# Sheet.net
KiCad netlist of a schematic drawn in Altium Designer
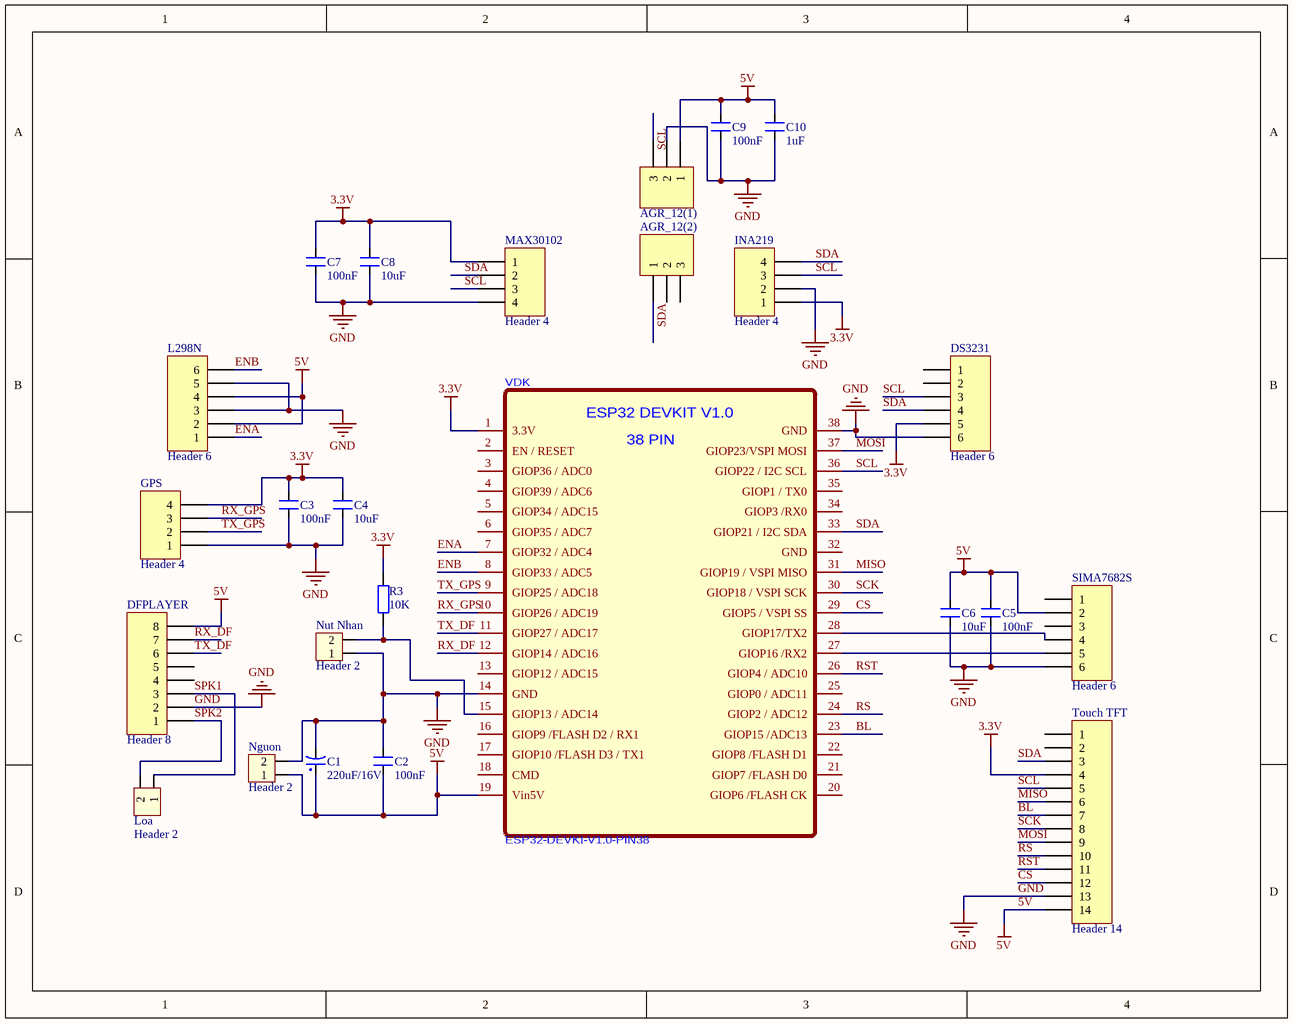
[diagram p0: Sheet.SchDoc]

(export (version "E")
  (design (tool "Eeschema 10.0.6"))
  (components
    (comp (ref "AGR_12(1)")
      (value "~")
      (footprint "HDR1X3")
      (description "Header, 3-Pin")
      (fields (field (name "PUBLISHER") "Altium Limited"))
      (libsource (lib "") (part "Header 3_1"))
    )
    (comp (ref "AGR_12(2)")
      (value "~")
      (footprint "HDR1X3")
      (description "Header, 3-Pin")
      (fields (field (name "PUBLISHER") "Altium Limited"))
      (libsource (lib "Altium_Devzone") (part "Header 3"))
    )
    (comp (ref "C1")
      (value "220uF/16V")
      (footprint "CP1.5/3.4")
      (description "Cap 1000uF/16V - 220uF/50V")
      (libsource (lib "My Library") (part "CP4"))
    )
    (comp (ref "C2")
      (value "100nF")
      (footprint "CN2")
      (description "Cap np 104 => 105pF")
      (libsource (lib "Altium_Devzone") (part "CN2"))
    )
    (comp (ref "C3")
      (value "100nF")
      (footprint "CN2")
      (description "Cap np 104 => 105pF")
      (libsource (lib "Altium_Devzone") (part "CN2"))
    )
    (comp (ref "C4")
      (value "10uF")
      (footprint "CN2")
      (description "Cap np 104 => 105pF")
      (libsource (lib "Altium_Devzone") (part "CN2"))
    )
    (comp (ref "C5")
      (value "100nF")
      (footprint "CN2")
      (description "Cap np 104 => 105pF")
      (libsource (lib "Altium_Devzone") (part "CN2"))
    )
    (comp (ref "C6")
      (value "10uF")
      (footprint "CN2")
      (description "Cap np 104 => 105pF")
      (libsource (lib "Altium_Devzone") (part "CN2"))
    )
    (comp (ref "C7")
      (value "100nF")
      (footprint "CN2")
      (description "Cap np 104 => 105pF")
      (libsource (lib "Altium_Devzone") (part "CN2"))
    )
    (comp (ref "C8")
      (value "10uF")
      (footprint "CN2")
      (description "Cap np 104 => 105pF")
      (libsource (lib "Altium_Devzone") (part "CN2"))
    )
    (comp (ref "C9")
      (value "100nF")
      (footprint "CN2")
      (description "Cap np 104 => 105pF")
      (libsource (lib "Altium_Devzone") (part "CN2"))
    )
    (comp (ref "C10")
      (value "1uF")
      (footprint "CN2")
      (description "Cap np 104 => 105pF")
      (libsource (lib "Altium_Devzone") (part "CN2"))
    )
    (comp (ref "DFPLAYER")
      (value "Header 8")
      (footprint "HDR1X8")
      (description "Header, 8-Pin")
      (fields (field (name "PUBLISHER") "Altium Limited"))
      (libsource (lib "Altium_Devzone") (part "Header 8"))
    )
    (comp (ref "DS3231")
      (value "Header 6")
      (footprint "HDR1X6")
      (description "Header, 6-Pin")
      (fields (field (name "PUBLISHER") "Altium Limited"))
      (libsource (lib "My Library") (part "Header 6"))
    )
    (comp (ref "GPS")
      (value "Header 4")
      (footprint "HDR1X4")
      (description "Header, 4-Pin")
      (fields (field (name "PUBLISHER") "Altium Limited"))
      (libsource (lib "") (part "Header 4_1"))
    )
    (comp (ref "INA219")
      (value "Header 4")
      (footprint "HDR1X4")
      (description "Header, 4-Pin")
      (fields (field (name "PUBLISHER") "Altium Limited"))
      (libsource (lib "") (part "Header 4_1"))
    )
    (comp (ref "L298N")
      (value "Header 6")
      (footprint "HDR1X6")
      (description "Header, 6-Pin")
      (fields (field (name "PUBLISHER") "Altium Limited"))
      (libsource (lib "Altium_Devzone") (part "Header 6"))
    )
    (comp (ref "Loa")
      (value "Header 2")
      (footprint "HED2")
      (description "Header 2 (Green)")
      (libsource (lib "") (part "Hed2_1"))
    )
    (comp (ref "MAX30102")
      (value "Header 4")
      (footprint "HDR1X4")
      (description "Header, 4-Pin")
      (fields (field (name "PUBLISHER") "Altium Limited"))
      (libsource (lib "My Library") (part "Header 4"))
    )
    (comp (ref "Nguon")
      (value "Header 2")
      (footprint "HED2")
      (description "Header 2 (Green)")
      (libsource (lib "My Library") (part "Hed2"))
    )
    (comp (ref "Nut Nhan")
      (value "Header 2")
      (footprint "HED2")
      (description "Header 2 (Green)")
      (libsource (lib "My Library") (part "Hed2"))
    )
    (comp (ref "R3")
      (value "10K")
      (footprint "DIEN TRO 1/4 W")
      (description "Resistor")
      (fields (field (name "Comment") "R0.4W") (field (name "PUBLISHER") "Altium Limited"))
      (libsource (lib "Altium_Devzone") (part "Res 1/4 W"))
    )
    (comp (ref "SIMA7682S")
      (value "Header 6")
      (footprint "HDR1X6")
      (description "Header, 6-Pin")
      (fields (field (name "PUBLISHER") "Altium Limited"))
      (libsource (lib "My Library") (part "Header 6"))
    )
    (comp (ref "Touch TFT")
      (value "Header 14")
      (footprint "HDR1X14")
      (description "Header, 14-Pin")
      (fields (field (name "PUBLISHER") "Altium Limited"))
      (libsource (lib "My Library") (part "Header 14"))
    )
    (comp (ref "VDK")
      (value "ESP32-DEVKI-V1.0-PIN38")
      (footprint "ESP32-DEVKIT-V1.0-38PIN")
      (libsource (lib "My Library") (part "ESP32-DEVKI-V1.0-PIN38"))
    )
  )
  (nets
    (net (code "1") (name "/BL") (class "Default")
      (node (ref "Touch TFT") (pin "7") (pinfunction "7_7") (pintype "passive"))
      (node (ref "VDK") (pin "23") (pinfunction "GIOP15_/ADC13_23") (pintype "passive"))
    )
    (net (code "2") (name "/CS") (class "Default")
      (node (ref "Touch TFT") (pin "12") (pinfunction "12_12") (pintype "passive"))
      (node (ref "VDK") (pin "29") (pinfunction "GIOP5_/_VSPI_SS_29") (pintype "passive"))
    )
    (net (code "3") (name "/ENA") (class "Default")
      (node (ref "L298N") (pin "1") (pinfunction "1_1") (pintype "passive"))
      (node (ref "VDK") (pin "7") (pinfunction "GIOP32_/_ADC4_7") (pintype "passive"))
    )
    (net (code "4") (name "/ENB") (class "Default")
      (node (ref "L298N") (pin "6") (pinfunction "6_6") (pintype "passive"))
      (node (ref "VDK") (pin "8") (pinfunction "GIOP33_/_ADC5_8") (pintype "passive"))
    )
    (net (code "5") (name "/MISO") (class "Default")
      (node (ref "Touch TFT") (pin "6") (pinfunction "6_6") (pintype "passive"))
      (node (ref "VDK") (pin "31") (pinfunction "GIOP19_/_VSPI_MISO_31") (pintype "passive"))
    )
    (net (code "6") (name "/MOSI") (class "Default")
      (node (ref "Touch TFT") (pin "9") (pinfunction "9_9") (pintype "passive"))
      (node (ref "VDK") (pin "37") (pinfunction "GIOP23/VSPI_MOSI_37") (pintype "passive"))
    )
    (net (code "7") (name "/RS") (class "Default")
      (node (ref "Touch TFT") (pin "10") (pinfunction "10_10") (pintype "passive"))
      (node (ref "VDK") (pin "24") (pinfunction "GIOP2_/_ADC12_24") (pintype "passive"))
    )
    (net (code "8") (name "/RST") (class "Default")
      (node (ref "Touch TFT") (pin "11") (pinfunction "11_11") (pintype "passive"))
      (node (ref "VDK") (pin "26") (pinfunction "GIOP4_/_ADC10_26") (pintype "passive"))
    )
    (net (code "9") (name "/RX_DF") (class "Default")
      (node (ref "DFPLAYER") (pin "7") (pinfunction "7_7") (pintype "passive"))
      (node (ref "VDK") (pin "12") (pinfunction "GIOP14_/_ADC16_12") (pintype "passive"))
    )
    (net (code "10") (name "/RX_GPS") (class "Default")
      (node (ref "GPS") (pin "3") (pinfunction "3_3") (pintype "passive"))
      (node (ref "VDK") (pin "10") (pinfunction "GIOP26_/_ADC19_10") (pintype "passive"))
    )
    (net (code "11") (name "/SCK") (class "Default")
      (node (ref "Touch TFT") (pin "8") (pinfunction "8_8") (pintype "passive"))
      (node (ref "VDK") (pin "30") (pinfunction "GIOP18_/_VSPI_SCK_30") (pintype "passive"))
    )
    (net (code "12") (name "/SCL") (class "Default")
      (node (ref "AGR_12(1)") (pin "3") (pinfunction "3_3") (pintype "passive"))
      (node (ref "DS3231") (pin "3") (pinfunction "3_3") (pintype "passive"))
      (node (ref "INA219") (pin "3") (pinfunction "3_3") (pintype "passive"))
      (node (ref "MAX30102") (pin "3") (pinfunction "3_3") (pintype "passive"))
      (node (ref "Touch TFT") (pin "5") (pinfunction "5_5") (pintype "passive"))
      (node (ref "VDK") (pin "36") (pinfunction "GIOP22_/_I2C_SCL_36") (pintype "passive"))
    )
    (net (code "13") (name "/SDA") (class "Default")
      (node (ref "AGR_12(2)") (pin "1") (pinfunction "1_1") (pintype "passive"))
      (node (ref "DS3231") (pin "4") (pinfunction "4_4") (pintype "passive"))
      (node (ref "INA219") (pin "4") (pinfunction "4_4") (pintype "passive"))
      (node (ref "MAX30102") (pin "2") (pinfunction "2_2") (pintype "passive"))
      (node (ref "Touch TFT") (pin "3") (pinfunction "3_3") (pintype "passive"))
      (node (ref "VDK") (pin "33") (pinfunction "GIOP21_/_I2C_SDA_33") (pintype "passive"))
    )
    (net (code "14") (name "/SPK1") (class "Default")
      (node (ref "DFPLAYER") (pin "3") (pinfunction "3_3") (pintype "passive"))
      (node (ref "Loa") (pin "1") (pinfunction "1_1") (pintype "passive"))
    )
    (net (code "15") (name "/SPK2") (class "Default")
      (node (ref "DFPLAYER") (pin "1") (pinfunction "1_1") (pintype "passive"))
      (node (ref "Loa") (pin "2") (pinfunction "2_2") (pintype "passive"))
    )
    (net (code "16") (name "/TX_DF") (class "Default")
      (node (ref "DFPLAYER") (pin "6") (pinfunction "6_6") (pintype "passive"))
      (node (ref "VDK") (pin "11") (pinfunction "GIOP27_/_ADC17_11") (pintype "passive"))
    )
    (net (code "17") (name "/TX_GPS") (class "Default")
      (node (ref "GPS") (pin "2") (pinfunction "2_2") (pintype "passive"))
      (node (ref "VDK") (pin "9") (pinfunction "GIOP25_/_ADC18_9") (pintype "passive"))
    )
    (net (code "18") (name "3.3V") (class "Default")
      (node (ref "C3") (pin "2") (pinfunction "2_2") (pintype "passive"))
      (node (ref "C4") (pin "2") (pinfunction "2_2") (pintype "passive"))
      (node (ref "C7") (pin "2") (pinfunction "2_2") (pintype "passive"))
      (node (ref "C8") (pin "2") (pinfunction "2_2") (pintype "passive"))
      (node (ref "DS3231") (pin "5") (pinfunction "5_5") (pintype "passive"))
      (node (ref "GPS") (pin "4") (pinfunction "4_4") (pintype "passive"))
      (node (ref "INA219") (pin "1") (pinfunction "1_1") (pintype "passive"))
      (node (ref "MAX30102") (pin "1") (pinfunction "1_1") (pintype "passive"))
      (node (ref "R3") (pin "2") (pinfunction "2_2") (pintype "passive"))
      (node (ref "Touch TFT") (pin "4") (pinfunction "4_4") (pintype "passive"))
      (node (ref "VDK") (pin "1") (pinfunction "3.3V_1") (pintype "passive"))
    )
    (net (code "19") (name "5V") (class "Default")
      (node (ref "AGR_12(1)") (pin "1") (pinfunction "1_1") (pintype "passive"))
      (node (ref "C1") (pin "1") (pinfunction "1_1") (pintype "passive"))
      (node (ref "C10") (pin "2") (pinfunction "2_2") (pintype "passive"))
      (node (ref "C2") (pin "1") (pinfunction "1_1") (pintype "passive"))
      (node (ref "C5") (pin "2") (pinfunction "2_2") (pintype "passive"))
      (node (ref "C6") (pin "2") (pinfunction "2_2") (pintype "passive"))
      (node (ref "C9") (pin "2") (pinfunction "2_2") (pintype "passive"))
      (node (ref "DFPLAYER") (pin "8") (pinfunction "8_8") (pintype "passive"))
      (node (ref "L298N") (pin "2") (pinfunction "2_2") (pintype "passive"))
      (node (ref "L298N") (pin "4") (pinfunction "4_4") (pintype "passive"))
      (node (ref "Nguon") (pin "1") (pinfunction "1_1") (pintype "passive"))
      (node (ref "SIMA7682S") (pin "2") (pinfunction "2_2") (pintype "passive"))
      (node (ref "Touch TFT") (pin "14") (pinfunction "14_14") (pintype "passive"))
      (node (ref "VDK") (pin "19") (pinfunction "Vin5V_19") (pintype "passive"))
    )
    (net (code "20") (name "GND") (class "Default")
      (node (ref "AGR_12(1)") (pin "2") (pinfunction "2_2") (pintype "passive"))
      (node (ref "C1") (pin "2") (pinfunction "2_2") (pintype "passive"))
      (node (ref "C10") (pin "1") (pinfunction "1_1") (pintype "passive"))
      (node (ref "C2") (pin "2") (pinfunction "2_2") (pintype "passive"))
      (node (ref "C3") (pin "1") (pinfunction "1_1") (pintype "passive"))
      (node (ref "C4") (pin "1") (pinfunction "1_1") (pintype "passive"))
      (node (ref "C5") (pin "1") (pinfunction "1_1") (pintype "passive"))
      (node (ref "C6") (pin "1") (pinfunction "1_1") (pintype "passive"))
      (node (ref "C7") (pin "1") (pinfunction "1_1") (pintype "passive"))
      (node (ref "C8") (pin "1") (pinfunction "1_1") (pintype "passive"))
      (node (ref "C9") (pin "1") (pinfunction "1_1") (pintype "passive"))
      (node (ref "DFPLAYER") (pin "2") (pinfunction "2_2") (pintype "passive"))
      (node (ref "DS3231") (pin "6") (pinfunction "6_6") (pintype "passive"))
      (node (ref "GPS") (pin "1") (pinfunction "1_1") (pintype "passive"))
      (node (ref "INA219") (pin "2") (pinfunction "2_2") (pintype "passive"))
      (node (ref "L298N") (pin "3") (pinfunction "3_3") (pintype "passive"))
      (node (ref "L298N") (pin "5") (pinfunction "5_5") (pintype "passive"))
      (node (ref "MAX30102") (pin "4") (pinfunction "4_4") (pintype "passive"))
      (node (ref "Nguon") (pin "2") (pinfunction "2_2") (pintype "passive"))
      (node (ref "Nut Nhan") (pin "1") (pinfunction "1_1") (pintype "passive"))
      (node (ref "SIMA7682S") (pin "6") (pinfunction "6_6") (pintype "passive"))
      (node (ref "Touch TFT") (pin "13") (pinfunction "13_13") (pintype "passive"))
      (node (ref "VDK") (pin "14") (pinfunction "GND_14") (pintype "passive"))
      (node (ref "VDK") (pin "38") (pinfunction "GND_38") (pintype "passive"))
    )
    (net (code "21") (name "Net-(VDK-GIOP13_{slash}_ADC14)") (class "Default")
      (node (ref "Nut Nhan") (pin "2") (pinfunction "2_2") (pintype "passive"))
      (node (ref "R3") (pin "1") (pinfunction "1_1") (pintype "passive"))
      (node (ref "VDK") (pin "15") (pinfunction "GIOP13_/_ADC14_15") (pintype "passive"))
    )
    (net (code "22") (name "Net-(VDK-GIOP16_{slash}RX2)") (class "Default")
      (node (ref "SIMA7682S") (pin "5") (pinfunction "5_5") (pintype "passive"))
      (node (ref "VDK") (pin "27") (pinfunction "GIOP16_/RX2_27") (pintype "passive"))
    )
    (net (code "23") (name "Net-(VDK-GIOP17{slash}TX2)") (class "Default")
      (node (ref "SIMA7682S") (pin "4") (pinfunction "4_4") (pintype "passive"))
      (node (ref "VDK") (pin "28") (pinfunction "GIOP17/TX2_28") (pintype "passive"))
    )
    (net (code "24") (name "unconnected-(AGR_12(2)-Pad2)") (class "Default")
      (node (ref "AGR_12(2)") (pin "2") (pinfunction "2_2") (pintype "passive"))
    )
    (net (code "25") (name "unconnected-(AGR_12(2)-Pad3)") (class "Default")
      (node (ref "AGR_12(2)") (pin "3") (pinfunction "3_3") (pintype "passive"))
    )
    (net (code "26") (name "unconnected-(DFPLAYER-Pad4)") (class "Default")
      (node (ref "DFPLAYER") (pin "4") (pinfunction "4_4") (pintype "passive"))
    )
    (net (code "27") (name "unconnected-(DFPLAYER-Pad5)") (class "Default")
      (node (ref "DFPLAYER") (pin "5") (pinfunction "5_5") (pintype "passive"))
    )
    (net (code "28") (name "unconnected-(DS3231-Pad1)") (class "Default")
      (node (ref "DS3231") (pin "1") (pinfunction "1_1") (pintype "passive"))
    )
    (net (code "29") (name "unconnected-(DS3231-Pad2)") (class "Default")
      (node (ref "DS3231") (pin "2") (pinfunction "2_2") (pintype "passive"))
    )
    (net (code "30") (name "unconnected-(SIMA7682S-Pad1)") (class "Default")
      (node (ref "SIMA7682S") (pin "1") (pinfunction "1_1") (pintype "passive"))
    )
    (net (code "31") (name "unconnected-(SIMA7682S-Pad3)") (class "Default")
      (node (ref "SIMA7682S") (pin "3") (pinfunction "3_3") (pintype "passive"))
    )
    (net (code "32") (name "unconnected-(Touch TFT-Pad1)") (class "Default")
      (node (ref "Touch TFT") (pin "1") (pinfunction "1_1") (pintype "passive"))
    )
    (net (code "33") (name "unconnected-(Touch TFT-Pad2)") (class "Default")
      (node (ref "Touch TFT") (pin "2") (pinfunction "2_2") (pintype "passive"))
    )
    (net (code "34") (name "unconnected-(VDK-CMD-Pad18)") (class "Default")
      (node (ref "VDK") (pin "18") (pinfunction "CMD_18") (pintype "passive"))
    )
    (net (code "35") (name "unconnected-(VDK-EN_{slash}_RESET-Pad2)") (class "Default")
      (node (ref "VDK") (pin "2") (pinfunction "EN_/_RESET_2") (pintype "passive"))
    )
    (net (code "36") (name "unconnected-(VDK-GIOP0_{slash}_ADC11-Pad25)") (class "Default")
      (node (ref "VDK") (pin "25") (pinfunction "GIOP0_/_ADC11_25") (pintype "passive"))
    )
    (net (code "37") (name "unconnected-(VDK-GIOP1_{slash}_TX0-Pad35)") (class "Default")
      (node (ref "VDK") (pin "35") (pinfunction "GIOP1_/_TX0_35") (pintype "passive"))
    )
    (net (code "38") (name "unconnected-(VDK-GIOP3_{slash}RX0-Pad34)") (class "Default")
      (node (ref "VDK") (pin "34") (pinfunction "GIOP3_/RX0_34") (pintype "passive"))
    )
    (net (code "39") (name "unconnected-(VDK-GIOP6_{slash}FLASH_CK-Pad20)") (class "Default")
      (node (ref "VDK") (pin "20") (pinfunction "GIOP6_/FLASH_CK_20") (pintype "passive"))
    )
    (net (code "40") (name "unconnected-(VDK-GIOP7_{slash}FLASH_D0-Pad21)") (class "Default")
      (node (ref "VDK") (pin "21") (pinfunction "GIOP7_/FLASH_D0_21") (pintype "passive"))
    )
    (net (code "41") (name "unconnected-(VDK-GIOP8_{slash}FLASH_D1-Pad22)") (class "Default")
      (node (ref "VDK") (pin "22") (pinfunction "GIOP8_/FLASH_D1_22") (pintype "passive"))
    )
    (net (code "42") (name "unconnected-(VDK-GIOP9_{slash}FLASH_D2_{slash}_RX1-Pad16)") (class "Default")
      (node (ref "VDK") (pin "16") (pinfunction "GIOP9_/FLASH_D2_/_RX1_16") (pintype "passive"))
    )
    (net (code "43") (name "unconnected-(VDK-GIOP10_{slash}FLASH_D3_{slash}_TX1-Pad17)") (class "Default")
      (node (ref "VDK") (pin "17") (pinfunction "GIOP10_/FLASH_D3_/_TX1_17") (pintype "passive"))
    )
    (net (code "44") (name "unconnected-(VDK-GIOP12_{slash}_ADC15-Pad13)") (class "Default")
      (node (ref "VDK") (pin "13") (pinfunction "GIOP12_/_ADC15_13") (pintype "passive"))
    )
    (net (code "45") (name "unconnected-(VDK-GIOP34_{slash}_ADC15-Pad5)") (class "Default")
      (node (ref "VDK") (pin "5") (pinfunction "GIOP34_/_ADC15_5") (pintype "passive"))
    )
    (net (code "46") (name "unconnected-(VDK-GIOP35_{slash}_ADC7-Pad6)") (class "Default")
      (node (ref "VDK") (pin "6") (pinfunction "GIOP35_/_ADC7_6") (pintype "passive"))
    )
    (net (code "47") (name "unconnected-(VDK-GIOP36_{slash}_ADC0-Pad3)") (class "Default")
      (node (ref "VDK") (pin "3") (pinfunction "GIOP36_/_ADC0_3") (pintype "passive"))
    )
    (net (code "48") (name "unconnected-(VDK-GIOP39_{slash}_ADC6-Pad4)") (class "Default")
      (node (ref "VDK") (pin "4") (pinfunction "GIOP39_/_ADC6_4") (pintype "passive"))
    )
    (net (code "49") (name "unconnected-(VDK-GND-Pad32)") (class "Default")
      (node (ref "VDK") (pin "32") (pinfunction "GND_32") (pintype "passive"))
    )
  )
)
